# F200s.net
KiCad netlist of a schematic drawn in Altium Designer
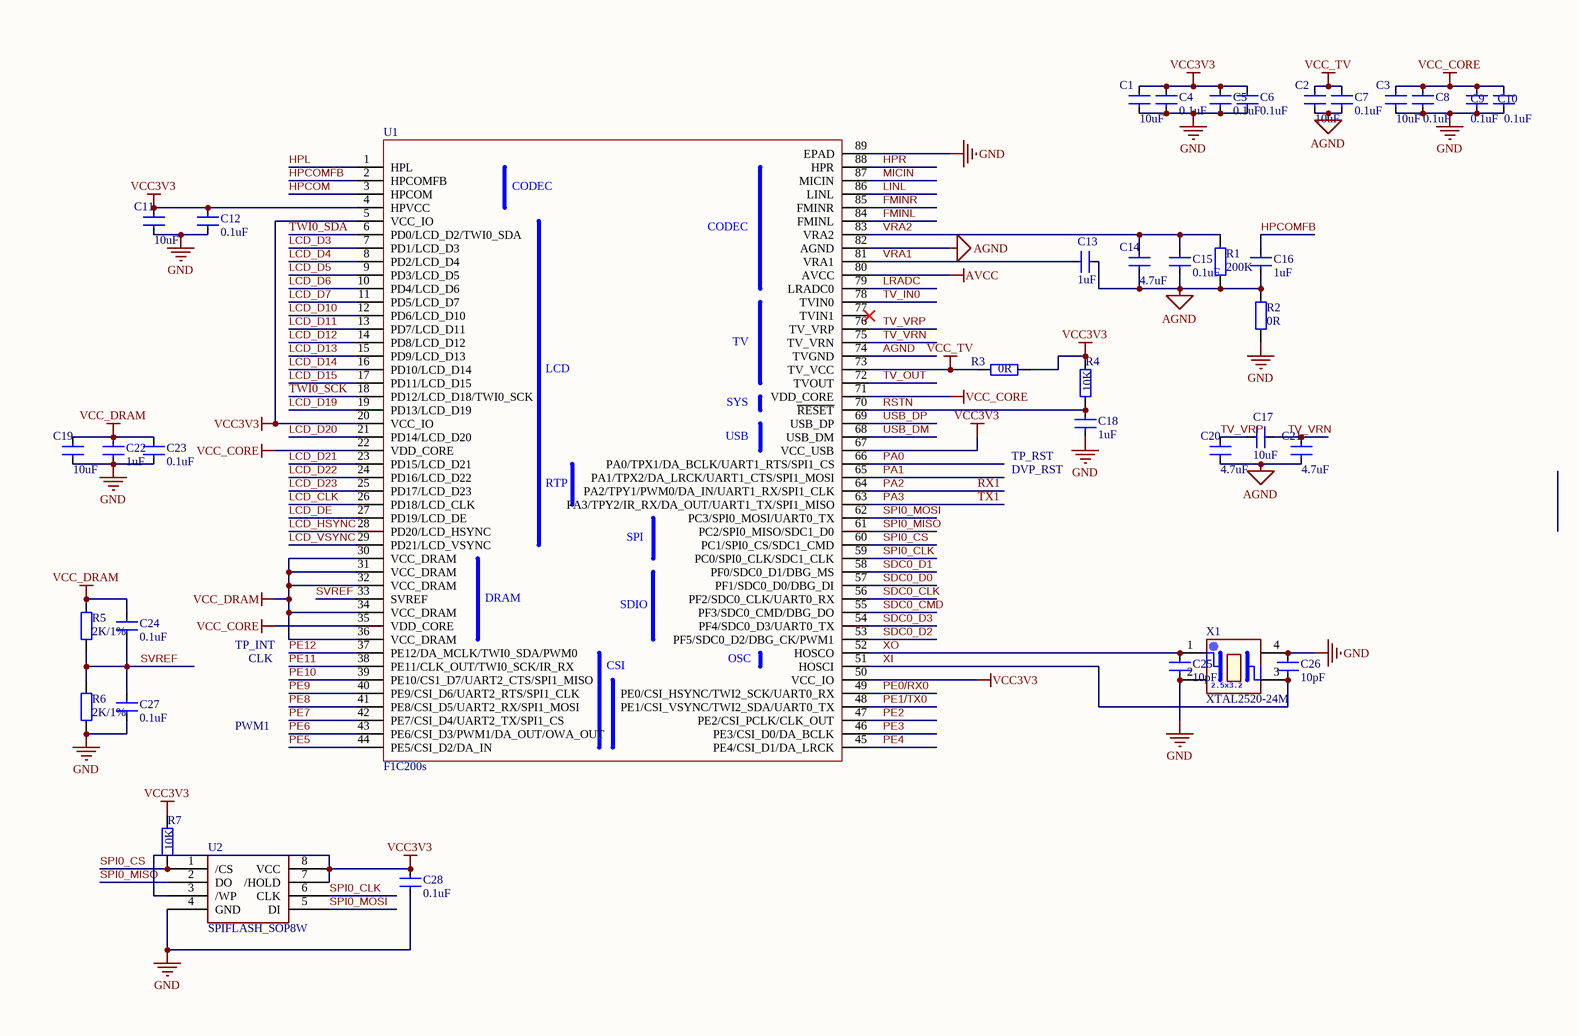
[diagram p0: F200s.SchDoc]

(export (version "E")
  (design (tool "Eeschema 10.0.6"))
  (components
    (comp (ref "C1")
      (value "10uF")
      (footprint "C0402")
      (description "普通小电容")
      (libsource (lib "f1c200s") (part "CAP"))
    )
    (comp (ref "C2")
      (value "10uF")
      (footprint "C0402")
      (description "普通小电容")
      (libsource (lib "f1c200s") (part "CAP"))
    )
    (comp (ref "C3")
      (value "10uF")
      (footprint "C0402")
      (description "普通小电容")
      (libsource (lib "f1c200s") (part "CAP"))
    )
    (comp (ref "C4")
      (value "0.1uF")
      (footprint "C0402")
      (description "普通小电容")
      (libsource (lib "f1c200s") (part "CAP"))
    )
    (comp (ref "C5")
      (value "0.1uF")
      (footprint "C0402")
      (description "普通小电容")
      (libsource (lib "f1c200s") (part "CAP"))
    )
    (comp (ref "C6")
      (value "0.1uF")
      (footprint "C0402")
      (description "普通小电容")
      (libsource (lib "f1c200s") (part "CAP"))
    )
    (comp (ref "C7")
      (value "0.1uF")
      (footprint "C0402")
      (description "普通小电容")
      (libsource (lib "f1c200s") (part "CAP"))
    )
    (comp (ref "C8")
      (value "0.1uF")
      (footprint "C0402")
      (description "普通小电容")
      (libsource (lib "f1c200s") (part "CAP"))
    )
    (comp (ref "C9")
      (value "0.1uF")
      (footprint "C0402")
      (description "普通小电容")
      (libsource (lib "f1c200s") (part "CAP"))
    )
    (comp (ref "C10")
      (value "0.1uF")
      (footprint "C0402")
      (description "普通小电容")
      (libsource (lib "f1c200s") (part "CAP"))
    )
    (comp (ref "C11")
      (value "10uF")
      (footprint "C0402")
      (description "普通小电容")
      (libsource (lib "f1c200s") (part "CAP"))
    )
    (comp (ref "C12")
      (value "0.1uF")
      (footprint "C0402")
      (description "普通小电容")
      (libsource (lib "f1c200s") (part "CAP"))
    )
    (comp (ref "C13")
      (value "1uF")
      (footprint "C0402")
      (description "普通小电容")
      (libsource (lib "f1c200s") (part "CAP"))
    )
    (comp (ref "C14")
      (value "4.7uF")
      (footprint "C0402")
      (description "普通小电容")
      (libsource (lib "f1c200s") (part "CAP"))
    )
    (comp (ref "C15")
      (value "0.1uF")
      (footprint "C0402")
      (description "普通小电容")
      (libsource (lib "f1c200s") (part "CAP"))
    )
    (comp (ref "C16")
      (value "1uF")
      (footprint "C0402")
      (description "普通小电容")
      (libsource (lib "f1c200s") (part "CAP"))
    )
    (comp (ref "C17")
      (value "10uF")
      (footprint "C0402")
      (description "普通小电容")
      (libsource (lib "f1c200s") (part "CAP"))
    )
    (comp (ref "C18")
      (value "1uF")
      (footprint "C0402")
      (description "普通小电容")
      (libsource (lib "f1c200s") (part "CAP"))
    )
    (comp (ref "C19")
      (value "10uF")
      (footprint "C0402")
      (description "普通小电容")
      (libsource (lib "f1c200s") (part "CAP"))
    )
    (comp (ref "C20")
      (value "4.7uF")
      (footprint "C0402")
      (description "普通小电容")
      (libsource (lib "f1c200s") (part "CAP"))
    )
    (comp (ref "C21")
      (value "4.7uF")
      (footprint "C0402")
      (description "普通小电容")
      (libsource (lib "f1c200s") (part "CAP"))
    )
    (comp (ref "C22")
      (value "1uF")
      (footprint "C0402")
      (description "普通小电容")
      (libsource (lib "f1c200s") (part "CAP"))
    )
    (comp (ref "C23")
      (value "0.1uF")
      (footprint "C0402")
      (description "普通小电容")
      (libsource (lib "f1c200s") (part "CAP"))
    )
    (comp (ref "C24")
      (value "0.1uF")
      (footprint "C0402")
      (description "普通小电容")
      (libsource (lib "f1c200s") (part "CAP"))
    )
    (comp (ref "C25")
      (value "10pF")
      (footprint "C0402")
      (description "普通小电容")
      (libsource (lib "f1c200s") (part "CAP"))
    )
    (comp (ref "C26")
      (value "10pF")
      (footprint "C0402")
      (description "普通小电容")
      (libsource (lib "f1c200s") (part "CAP"))
    )
    (comp (ref "C27")
      (value "0.1uF")
      (footprint "C0402")
      (description "普通小电容")
      (libsource (lib "f1c200s") (part "CAP"))
    )
    (comp (ref "C28")
      (value "0.1uF")
      (footprint "C0402")
      (description "普通小电容")
      (libsource (lib "f1c200s") (part "CAP"))
    )
    (comp (ref "R1")
      (value "200K")
      (footprint "R0402")
      (description "普通电阻")
      (libsource (lib "LIB_MANGO") (part "RES"))
    )
    (comp (ref "R2")
      (value "0R")
      (footprint "R0402")
      (description "普通电阻")
      (libsource (lib "LIB_MANGO") (part "RES"))
    )
    (comp (ref "R3")
      (value "0R")
      (footprint "R0402")
      (description "普通电阻")
      (libsource (lib "") (part "RES_1"))
    )
    (comp (ref "R4")
      (value "10K")
      (footprint "R0402")
      (description "普通电阻")
      (libsource (lib "LIB_MANGO") (part "RES"))
    )
    (comp (ref "R5")
      (value "2K/1%")
      (footprint "R0402")
      (description "普通电阻")
      (libsource (lib "LIB_MANGO") (part "RES"))
    )
    (comp (ref "R6")
      (value "2K/1%")
      (footprint "R0402")
      (description "普通电阻")
      (libsource (lib "LIB_MANGO") (part "RES"))
    )
    (comp (ref "R7")
      (value "10K")
      (footprint "R0402")
      (description "普通电阻")
      (libsource (lib "LIB_MANGO") (part "RES"))
    )
    (comp (ref "U1")
      (value "F1C200s")
      (footprint "QFN40P1000X1000X85_HS-89N")
      (libsource (lib "A") (part "F1C200s"))
    )
    (comp (ref "U2")
      (value "SPIFLASH_SOP8W")
      (footprint "WSON-SPIFLASH")
      (libsource (lib "LIB_MANGO") (part "SPIFLASH_SOP8W"))
    )
    (comp (ref "X1")
      (value "XTAL2520-24M")
      (footprint "XTAL2520")
      (libsource (lib "LIB_MANGO") (part "XTAL3225"))
    )
  )
  (nets
    (net (code "1") (name "/FMINL") (class "Default")
      (node (ref "U1") (pin "84") (pinfunction "FMINL_84") (pintype "passive"))
    )
    (net (code "2") (name "/FMINR") (class "Default")
      (node (ref "U1") (pin "85") (pinfunction "FMINR_85") (pintype "passive"))
    )
    (net (code "3") (name "/HPCOM") (class "Default")
      (node (ref "U1") (pin "3") (pinfunction "HPCOM_3") (pintype "passive"))
    )
    (net (code "4") (name "/HPCOMFB") (class "Default")
      (node (ref "C16") (pin "1") (pinfunction "1_1") (pintype "passive"))
      (node (ref "U1") (pin "2") (pinfunction "HPCOMFB_2") (pintype "passive"))
    )
    (net (code "5") (name "/HPL") (class "Default")
      (node (ref "U1") (pin "1") (pinfunction "HPL_1") (pintype "passive"))
    )
    (net (code "6") (name "/HPR") (class "Default")
      (node (ref "U1") (pin "88") (pinfunction "HPR_88") (pintype "passive"))
    )
    (net (code "7") (name "/LCD_CLK") (class "Default")
      (node (ref "U1") (pin "26") (pinfunction "PD18/LCD_CLK_26") (pintype "passive"))
    )
    (net (code "8") (name "/LCD_D3") (class "Default")
      (node (ref "U1") (pin "7") (pinfunction "PD1/LCD_D3_7") (pintype "passive"))
    )
    (net (code "9") (name "/LCD_D4") (class "Default")
      (node (ref "U1") (pin "8") (pinfunction "PD2/LCD_D4_8") (pintype "passive"))
    )
    (net (code "10") (name "/LCD_D5") (class "Default")
      (node (ref "U1") (pin "9") (pinfunction "PD3/LCD_D5_9") (pintype "passive"))
    )
    (net (code "11") (name "/LCD_D6") (class "Default")
      (node (ref "U1") (pin "10") (pinfunction "PD4/LCD_D6_10") (pintype "passive"))
    )
    (net (code "12") (name "/LCD_D7") (class "Default")
      (node (ref "U1") (pin "11") (pinfunction "PD5/LCD_D7_11") (pintype "passive"))
    )
    (net (code "13") (name "/LCD_D10") (class "Default")
      (node (ref "U1") (pin "12") (pinfunction "PD6/LCD_D10_12") (pintype "passive"))
    )
    (net (code "14") (name "/LCD_D11") (class "Default")
      (node (ref "U1") (pin "13") (pinfunction "PD7/LCD_D11_13") (pintype "passive"))
    )
    (net (code "15") (name "/LCD_D12") (class "Default")
      (node (ref "U1") (pin "14") (pinfunction "PD8/LCD_D12_14") (pintype "passive"))
    )
    (net (code "16") (name "/LCD_D13") (class "Default")
      (node (ref "U1") (pin "15") (pinfunction "PD9/LCD_D13_15") (pintype "passive"))
    )
    (net (code "17") (name "/LCD_D14") (class "Default")
      (node (ref "U1") (pin "16") (pinfunction "PD10/LCD_D14_16") (pintype "passive"))
    )
    (net (code "18") (name "/LCD_D15") (class "Default")
      (node (ref "U1") (pin "17") (pinfunction "PD11/LCD_D15_17") (pintype "passive"))
    )
    (net (code "19") (name "/LCD_D19") (class "Default")
      (node (ref "U1") (pin "19") (pinfunction "PD13/LCD_D19_19") (pintype "passive"))
    )
    (net (code "20") (name "/LCD_D20") (class "Default")
      (node (ref "U1") (pin "21") (pinfunction "PD14/LCD_D20_21") (pintype "passive"))
    )
    (net (code "21") (name "/LCD_D21") (class "Default")
      (node (ref "U1") (pin "23") (pinfunction "PD15/LCD_D21_23") (pintype "passive"))
    )
    (net (code "22") (name "/LCD_D22") (class "Default")
      (node (ref "U1") (pin "24") (pinfunction "PD16/LCD_D22_24") (pintype "passive"))
    )
    (net (code "23") (name "/LCD_D23") (class "Default")
      (node (ref "U1") (pin "25") (pinfunction "PD17/LCD_D23_25") (pintype "passive"))
    )
    (net (code "24") (name "/LCD_DE") (class "Default")
      (node (ref "U1") (pin "27") (pinfunction "PD19/LCD_DE_27") (pintype "passive"))
    )
    (net (code "25") (name "/LCD_HSYNC") (class "Default")
      (node (ref "U1") (pin "28") (pinfunction "PD20/LCD_HSYNC_28") (pintype "passive"))
    )
    (net (code "26") (name "/LCD_VSYNC") (class "Default")
      (node (ref "U1") (pin "29") (pinfunction "PD21/LCD_VSYNC_29") (pintype "passive"))
    )
    (net (code "27") (name "/LINL") (class "Default")
      (node (ref "U1") (pin "86") (pinfunction "LINL_86") (pintype "passive"))
    )
    (net (code "28") (name "/LRADC") (class "Default")
      (node (ref "U1") (pin "79") (pinfunction "LRADC0_79") (pintype "passive"))
    )
    (net (code "29") (name "/MICIN") (class "Default")
      (node (ref "U1") (pin "87") (pinfunction "MICIN_87") (pintype "passive"))
    )
    (net (code "30") (name "/PA0") (class "Default")
      (node (ref "U1") (pin "66") (pinfunction "PA0/TPX1/DA_BCLK/UART1_RTS/SPI1_CS_66") (pintype "passive"))
    )
    (net (code "31") (name "/PA1") (class "Default")
      (node (ref "U1") (pin "65") (pinfunction "PA1/TPX2/DA_LRCK/UART1_CTS/SPI1_MOSI_65") (pintype "passive"))
    )
    (net (code "32") (name "/PA2") (class "Default")
      (node (ref "U1") (pin "64") (pinfunction "PA2/TPY1/PWM0/DA_IN/UART1_RX/SPI1_CLK_64") (pintype "passive"))
    )
    (net (code "33") (name "/PA3") (class "Default")
      (node (ref "U1") (pin "63") (pinfunction "PA3/TPY2/IR_RX/DA_OUT/UART1_TX/SPI1_MISO_63") (pintype "passive"))
    )
    (net (code "34") (name "/PE0{slash}RX0") (class "Default")
      (node (ref "U1") (pin "49") (pinfunction "PE0/CSI_HSYNC/TWI2_SCK/UART0_RX_49") (pintype "passive"))
    )
    (net (code "35") (name "/PE1{slash}TX0") (class "Default")
      (node (ref "U1") (pin "48") (pinfunction "PE1/CSI_VSYNC/TWI2_SDA/UART0_TX_48") (pintype "passive"))
    )
    (net (code "36") (name "/PE2") (class "Default")
      (node (ref "U1") (pin "47") (pinfunction "PE2/CSI_PCLK/CLK_OUT_47") (pintype "passive"))
    )
    (net (code "37") (name "/PE3") (class "Default")
      (node (ref "U1") (pin "46") (pinfunction "PE3/CSI_D0/DA_BCLK_46") (pintype "passive"))
    )
    (net (code "38") (name "/PE4") (class "Default")
      (node (ref "U1") (pin "45") (pinfunction "PE4/CSI_D1/DA_LRCK_45") (pintype "passive"))
    )
    (net (code "39") (name "/PE5") (class "Default")
      (node (ref "U1") (pin "44") (pinfunction "PE5/CSI_D2/DA_IN_44") (pintype "passive"))
    )
    (net (code "40") (name "/PE6") (class "Default")
      (node (ref "U1") (pin "43") (pinfunction "PE6/CSI_D3/PWM1/DA_OUT/OWA_OUT_43") (pintype "passive"))
    )
    (net (code "41") (name "/PE7") (class "Default")
      (node (ref "U1") (pin "42") (pinfunction "PE7/CSI_D4/UART2_TX/SPI1_CS_42") (pintype "passive"))
    )
    (net (code "42") (name "/PE8") (class "Default")
      (node (ref "U1") (pin "41") (pinfunction "PE8/CSI_D5/UART2_RX/SPI1_MOSI_41") (pintype "passive"))
    )
    (net (code "43") (name "/PE9") (class "Default")
      (node (ref "U1") (pin "40") (pinfunction "PE9/CSI_D6/UART2_RTS/SPI1_CLK_40") (pintype "passive"))
    )
    (net (code "44") (name "/PE10") (class "Default")
      (node (ref "U1") (pin "39") (pinfunction "PE10/CS1_D7/UART2_CTS/SPI1_MISO_39") (pintype "passive"))
    )
    (net (code "45") (name "/PE11") (class "Default")
      (node (ref "U1") (pin "38") (pinfunction "PE11/CLK_OUT/TWI0_SCK/IR_RX_38") (pintype "passive"))
    )
    (net (code "46") (name "/PE12") (class "Default")
      (node (ref "U1") (pin "37") (pinfunction "PE12/DA_MCLK/TWI0_SDA/PWM0_37") (pintype "passive"))
    )
    (net (code "47") (name "/RSTN") (class "Default")
      (node (ref "C18") (pin "1") (pinfunction "1_1") (pintype "passive"))
      (node (ref "R4") (pin "1") (pinfunction "1_1") (pintype "passive"))
      (node (ref "U1") (pin "70") (pinfunction "~{RESET}_70") (pintype "passive"))
    )
    (net (code "48") (name "/SDC0_CLK") (class "Default")
      (node (ref "U1") (pin "56") (pinfunction "PF2/SDC0_CLK/UART0_RX_56") (pintype "passive"))
    )
    (net (code "49") (name "/SDC0_CMD") (class "Default")
      (node (ref "U1") (pin "55") (pinfunction "PF3/SDC0_CMD/DBG_DO_55") (pintype "passive"))
    )
    (net (code "50") (name "/SDC0_D0") (class "Default")
      (node (ref "U1") (pin "57") (pinfunction "PF1/SDC0_D0/DBG_DI_57") (pintype "passive"))
    )
    (net (code "51") (name "/SDC0_D1") (class "Default")
      (node (ref "U1") (pin "58") (pinfunction "PF0/SDC0_D1/DBG_MS_58") (pintype "passive"))
    )
    (net (code "52") (name "/SDC0_D2") (class "Default")
      (node (ref "U1") (pin "53") (pinfunction "PF5/SDC0_D2/DBG_CK/PWM1_53") (pintype "passive"))
    )
    (net (code "53") (name "/SDC0_D3") (class "Default")
      (node (ref "U1") (pin "54") (pinfunction "PF4/SDC0_D3/UART0_TX_54") (pintype "passive"))
    )
    (net (code "54") (name "/SPI0_CLK") (class "Default")
      (node (ref "U1") (pin "59") (pinfunction "PC0/SPI0_CLK/SDC1_CLK_59") (pintype "passive"))
      (node (ref "U2") (pin "6") (pinfunction "CLK_6") (pintype "passive"))
    )
    (net (code "55") (name "/SPI0_CS") (class "Default")
      (node (ref "R7") (pin "1") (pinfunction "1_1") (pintype "passive"))
      (node (ref "U1") (pin "60") (pinfunction "PC1/SPI0_CS/SDC1_CMD_60") (pintype "passive"))
      (node (ref "U2") (pin "1") (pinfunction "/CS_1") (pintype "passive"))
    )
    (net (code "56") (name "/SPI0_MISO") (class "Default")
      (node (ref "U1") (pin "61") (pinfunction "PC2/SPI0_MISO/SDC1_D0_61") (pintype "passive"))
      (node (ref "U2") (pin "2") (pinfunction "DO_2") (pintype "passive"))
    )
    (net (code "57") (name "/SPI0_MOSI") (class "Default")
      (node (ref "U1") (pin "62") (pinfunction "PC3/SPI0_MOSI/UART0_TX_62") (pintype "passive"))
      (node (ref "U2") (pin "5") (pinfunction "DI_5") (pintype "passive"))
    )
    (net (code "58") (name "/SVREF") (class "Default")
      (node (ref "C24") (pin "1") (pinfunction "1_1") (pintype "passive"))
      (node (ref "C27") (pin "2") (pinfunction "2_2") (pintype "passive"))
      (node (ref "R5") (pin "1") (pinfunction "1_1") (pintype "passive"))
      (node (ref "R6") (pin "2") (pinfunction "2_2") (pintype "passive"))
      (node (ref "U1") (pin "33") (pinfunction "SVREF_33") (pintype "passive"))
    )
    (net (code "59") (name "/TV_IN0") (class "Default")
      (node (ref "U1") (pin "78") (pinfunction "TVIN0_78") (pintype "passive"))
    )
    (net (code "60") (name "/TV_OUT") (class "Default")
      (node (ref "U1") (pin "72") (pinfunction "TVOUT_72") (pintype "passive"))
    )
    (net (code "61") (name "/TV_VRN") (class "Default")
      (node (ref "C17") (pin "1") (pinfunction "1_1") (pintype "passive"))
      (node (ref "C21") (pin "2") (pinfunction "2_2") (pintype "passive"))
      (node (ref "U1") (pin "75") (pinfunction "TV_VRN_75") (pintype "passive"))
    )
    (net (code "62") (name "/TV_VRP") (class "Default")
      (node (ref "C17") (pin "2") (pinfunction "2_2") (pintype "passive"))
      (node (ref "C20") (pin "2") (pinfunction "2_2") (pintype "passive"))
      (node (ref "U1") (pin "76") (pinfunction "TV_VRP_76") (pintype "passive"))
    )
    (net (code "63") (name "/TWI0_SCK") (class "Default")
      (node (ref "U1") (pin "18") (pinfunction "PD12/LCD_D18/TWI0_SCK_18") (pintype "passive"))
    )
    (net (code "64") (name "/TWI0_SDA") (class "Default")
      (node (ref "U1") (pin "6") (pinfunction "PD0/LCD_D2/TWI0_SDA_6") (pintype "passive"))
    )
    (net (code "65") (name "/USB_DM") (class "Default")
      (node (ref "U1") (pin "68") (pinfunction "USB_DM_68") (pintype "passive"))
    )
    (net (code "66") (name "/USB_DP") (class "Default")
      (node (ref "U1") (pin "69") (pinfunction "USB_DP_69") (pintype "passive"))
    )
    (net (code "67") (name "/VRA1") (class "Default")
      (node (ref "C13") (pin "1") (pinfunction "1_1") (pintype "passive"))
      (node (ref "U1") (pin "81") (pinfunction "VRA1_81") (pintype "passive"))
    )
    (net (code "68") (name "/VRA2") (class "Default")
      (node (ref "C14") (pin "2") (pinfunction "2_2") (pintype "passive"))
      (node (ref "C15") (pin "2") (pinfunction "2_2") (pintype "passive"))
      (node (ref "R1") (pin "2") (pinfunction "2_2") (pintype "passive"))
      (node (ref "U1") (pin "83") (pinfunction "VRA2_83") (pintype "passive"))
    )
    (net (code "69") (name "/XI") (class "Default")
      (node (ref "C26") (pin "1") (pinfunction "1_1") (pintype "passive"))
      (node (ref "U1") (pin "51") (pinfunction "HOSCI_51") (pintype "passive"))
      (node (ref "X1") (pin "3") (pinfunction "X2_3") (pintype "passive"))
    )
    (net (code "70") (name "/XO") (class "Default")
      (node (ref "C25") (pin "2") (pinfunction "2_2") (pintype "passive"))
      (node (ref "U1") (pin "52") (pinfunction "HOSCO_52") (pintype "passive"))
      (node (ref "X1") (pin "1") (pinfunction "X1_1") (pintype "passive"))
    )
    (net (code "71") (name "AGND") (class "Default")
      (node (ref "C13") (pin "2") (pinfunction "2_2") (pintype "passive"))
      (node (ref "C14") (pin "1") (pinfunction "1_1") (pintype "passive"))
      (node (ref "C15") (pin "1") (pinfunction "1_1") (pintype "passive"))
      (node (ref "C16") (pin "2") (pinfunction "2_2") (pintype "passive"))
      (node (ref "C2") (pin "1") (pinfunction "1_1") (pintype "passive"))
      (node (ref "C20") (pin "1") (pinfunction "1_1") (pintype "passive"))
      (node (ref "C21") (pin "1") (pinfunction "1_1") (pintype "passive"))
      (node (ref "C7") (pin "1") (pinfunction "1_1") (pintype "passive"))
      (node (ref "R1") (pin "1") (pinfunction "1_1") (pintype "passive"))
      (node (ref "R2") (pin "2") (pinfunction "2_2") (pintype "passive"))
      (node (ref "U1") (pin "74") (pinfunction "TVGND_74") (pintype "passive"))
      (node (ref "U1") (pin "82") (pinfunction "AGND_82") (pintype "passive"))
    )
    (net (code "72") (name "AVCC") (class "Default")
      (node (ref "U1") (pin "80") (pinfunction "AVCC_80") (pintype "passive"))
    )
    (net (code "73") (name "GND") (class "Default")
      (node (ref "C1") (pin "1") (pinfunction "1_1") (pintype "passive"))
      (node (ref "C10") (pin "1") (pinfunction "1_1") (pintype "passive"))
      (node (ref "C11") (pin "1") (pinfunction "1_1") (pintype "passive"))
      (node (ref "C12") (pin "2") (pinfunction "2_2") (pintype "passive"))
      (node (ref "C18") (pin "2") (pinfunction "2_2") (pintype "passive"))
      (node (ref "C19") (pin "1") (pinfunction "1_1") (pintype "passive"))
      (node (ref "C22") (pin "1") (pinfunction "1_1") (pintype "passive"))
      (node (ref "C23") (pin "1") (pinfunction "1_1") (pintype "passive"))
      (node (ref "C25") (pin "1") (pinfunction "1_1") (pintype "passive"))
      (node (ref "C26") (pin "2") (pinfunction "2_2") (pintype "passive"))
      (node (ref "C27") (pin "1") (pinfunction "1_1") (pintype "passive"))
      (node (ref "C28") (pin "1") (pinfunction "1_1") (pintype "passive"))
      (node (ref "C3") (pin "1") (pinfunction "1_1") (pintype "passive"))
      (node (ref "C4") (pin "1") (pinfunction "1_1") (pintype "passive"))
      (node (ref "C5") (pin "1") (pinfunction "1_1") (pintype "passive"))
      (node (ref "C6") (pin "1") (pinfunction "1_1") (pintype "passive"))
      (node (ref "C8") (pin "1") (pinfunction "1_1") (pintype "passive"))
      (node (ref "C9") (pin "1") (pinfunction "1_1") (pintype "passive"))
      (node (ref "R2") (pin "1") (pinfunction "1_1") (pintype "passive"))
      (node (ref "R6") (pin "1") (pinfunction "1_1") (pintype "passive"))
      (node (ref "U1") (pin "89") (pinfunction "EPAD_89") (pintype "passive"))
      (node (ref "U2") (pin "4") (pinfunction "GND_4") (pintype "passive"))
      (node (ref "X1") (pin "2") (pinfunction "NC1_2") (pintype "passive"))
      (node (ref "X1") (pin "4") (pinfunction "NC2_4") (pintype "passive"))
    )
    (net (code "74") (name "VCC3V3") (class "Default")
      (node (ref "C1") (pin "2") (pinfunction "2_2") (pintype "passive"))
      (node (ref "C11") (pin "2") (pinfunction "2_2") (pintype "passive"))
      (node (ref "C12") (pin "1") (pinfunction "1_1") (pintype "passive"))
      (node (ref "C28") (pin "2") (pinfunction "2_2") (pintype "passive"))
      (node (ref "C4") (pin "2") (pinfunction "2_2") (pintype "passive"))
      (node (ref "C5") (pin "2") (pinfunction "2_2") (pintype "passive"))
      (node (ref "C6") (pin "2") (pinfunction "2_2") (pintype "passive"))
      (node (ref "R3") (pin "1") (pinfunction "1_1") (pintype "passive"))
      (node (ref "R4") (pin "2") (pinfunction "2_2") (pintype "passive"))
      (node (ref "R7") (pin "2") (pinfunction "2_2") (pintype "passive"))
      (node (ref "U1") (pin "20") (pinfunction "VCC_IO_20") (pintype "passive"))
      (node (ref "U1") (pin "4") (pinfunction "HPVCC_4") (pintype "passive"))
      (node (ref "U1") (pin "5") (pinfunction "VCC_IO_5") (pintype "passive"))
      (node (ref "U1") (pin "50") (pinfunction "VCC_IO_50") (pintype "passive"))
      (node (ref "U1") (pin "67") (pinfunction "VCC_USB_67") (pintype "passive"))
      (node (ref "U2") (pin "3") (pinfunction "/WP_3") (pintype "passive"))
      (node (ref "U2") (pin "7") (pinfunction "/HOLD_7") (pintype "passive"))
      (node (ref "U2") (pin "8") (pinfunction "VCC_8") (pintype "passive"))
    )
    (net (code "75") (name "VCC_CORE") (class "Default")
      (node (ref "C10") (pin "2") (pinfunction "2_2") (pintype "passive"))
      (node (ref "C3") (pin "2") (pinfunction "2_2") (pintype "passive"))
      (node (ref "C8") (pin "2") (pinfunction "2_2") (pintype "passive"))
      (node (ref "C9") (pin "2") (pinfunction "2_2") (pintype "passive"))
      (node (ref "U1") (pin "22") (pinfunction "VDD_CORE_22") (pintype "passive"))
      (node (ref "U1") (pin "35") (pinfunction "VDD_CORE_35") (pintype "passive"))
      (node (ref "U1") (pin "71") (pinfunction "VDD_CORE_71") (pintype "passive"))
    )
    (net (code "76") (name "VCC_DRAM") (class "Default")
      (node (ref "C19") (pin "2") (pinfunction "2_2") (pintype "passive"))
      (node (ref "C22") (pin "2") (pinfunction "2_2") (pintype "passive"))
      (node (ref "C23") (pin "2") (pinfunction "2_2") (pintype "passive"))
      (node (ref "C24") (pin "2") (pinfunction "2_2") (pintype "passive"))
      (node (ref "R5") (pin "2") (pinfunction "2_2") (pintype "passive"))
      (node (ref "U1") (pin "30") (pinfunction "VCC_DRAM_30") (pintype "passive"))
      (node (ref "U1") (pin "31") (pinfunction "VCC_DRAM_31") (pintype "passive"))
      (node (ref "U1") (pin "32") (pinfunction "VCC_DRAM_32") (pintype "passive"))
      (node (ref "U1") (pin "34") (pinfunction "VCC_DRAM_34") (pintype "passive"))
      (node (ref "U1") (pin "36") (pinfunction "VCC_DRAM_36") (pintype "passive"))
    )
    (net (code "77") (name "VCC_TV") (class "Default")
      (node (ref "C2") (pin "2") (pinfunction "2_2") (pintype "passive"))
      (node (ref "C7") (pin "2") (pinfunction "2_2") (pintype "passive"))
      (node (ref "R3") (pin "2") (pinfunction "2_2") (pintype "passive"))
      (node (ref "U1") (pin "73") (pinfunction "TV_VCC_73") (pintype "passive"))
    )
    (net (code "78") (name "unconnected-(U1-TVIN1-Pad77)") (class "Default")
      (node (ref "U1") (pin "77") (pinfunction "TVIN1_77") (pintype "passive+no_connect"))
    )
  )
)
